# Fixed_Delay_Line.net
KiCad netlist of a schematic drawn in Altium Designer
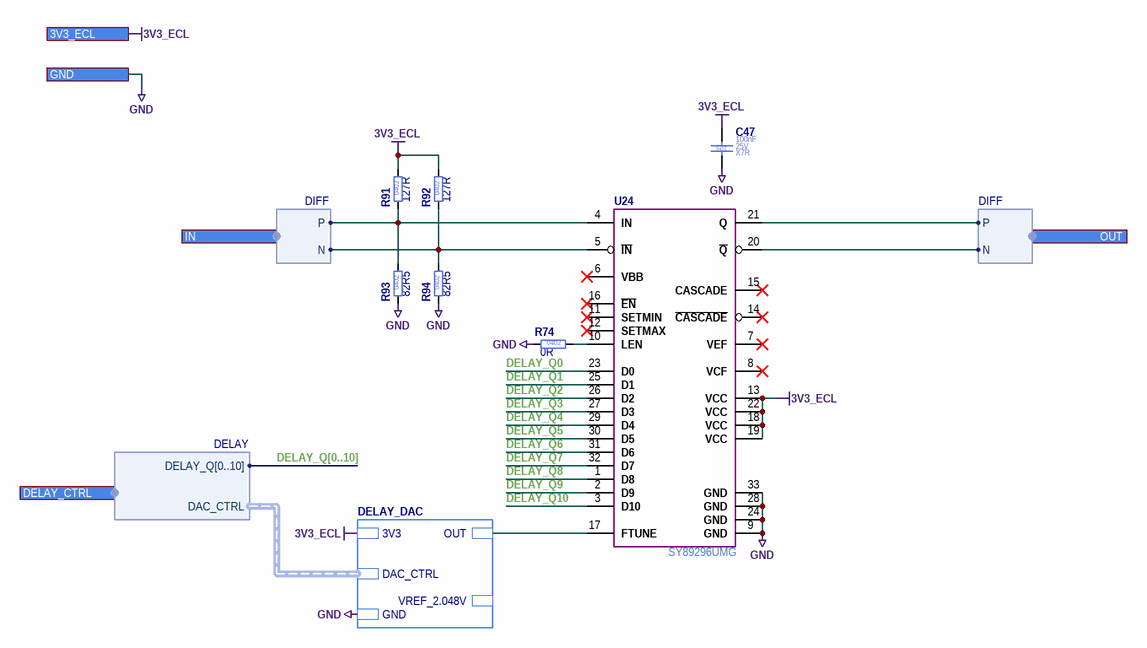
[diagram p0: Fixed_Delay_Line.SchDoc]

(export (version "E")
  (design (tool "Eeschema 10.0.6"))
  (components
    (comp (ref "C47")
      (value "C_100NF_25V_X7R_0402_10")
      (footprint "C_0402_1005")
      (description "Ceramic Capacitor")
      (fields
        (field (name "CASE/PACKAGE") "0402")
        (field (name "VOLTAGE RATING (DC)") "25V")
        (field (name "DIELECTRIC") "X7R")
        (field (name "CAPACITANCE") "100nF")
        (field (name "TOLERANCE") "10%")
        (field (name "MANUFACTURER PART NUMBER") "EMK105B7104KV-F")
      )
      (libsource (lib "7Sigma") (part "C"))
    )
    (comp (ref "R74")
      (value "R_0R_0402_1")
      (footprint "R_0402_1005")
      (description "Thick Film Resistor")
      (fields
        (field (name "RESISTANCE") "0R")
        (field (name "CASE/PACKAGE") "0402")
        (field (name "TOLERANCE") "1%")
        (field (name "MANUFACTURER") "Yageo")
      )
      (libsource (lib "7Sigma") (part "R"))
    )
    (comp (ref "R91")
      (value "R_127R_0402_1")
      (footprint "R_0402_1005")
      (description "Thick Film Resistor")
      (fields
        (field (name "RESISTANCE") "127R")
        (field (name "CASE/PACKAGE") "0402")
        (field (name "TOLERANCE") "1%")
        (field (name "MANUFACTURER") "Yageo")
      )
      (libsource (lib "7Sigma") (part "R"))
    )
    (comp (ref "R92")
      (value "R_127R_0402_1")
      (footprint "R_0402_1005")
      (description "Thick Film Resistor")
      (fields
        (field (name "RESISTANCE") "127R")
        (field (name "CASE/PACKAGE") "0402")
        (field (name "TOLERANCE") "1%")
        (field (name "MANUFACTURER") "Yageo")
      )
      (libsource (lib "7Sigma") (part "R"))
    )
    (comp (ref "R93")
      (value "R_82R5_0402_1")
      (footprint "R_0402_1005")
      (description "Thick Film Resistor")
      (fields
        (field (name "RESISTANCE") "82R5")
        (field (name "CASE/PACKAGE") "0402")
        (field (name "TOLERANCE") "1%")
        (field (name "MANUFACTURER") "Yageo")
      )
      (libsource (lib "7Sigma") (part "R"))
    )
    (comp (ref "R94")
      (value "R_82R5_0402_1")
      (footprint "R_0402_1005")
      (description "Thick Film Resistor")
      (fields
        (field (name "RESISTANCE") "82R5")
        (field (name "CASE/PACKAGE") "0402")
        (field (name "TOLERANCE") "1%")
        (field (name "MANUFACTURER") "Yageo")
      )
      (libsource (lib "7Sigma") (part "R"))
    )
    (comp (ref "U24")
      (value "SY89296UMG")
      (footprint "QFN50P500X500X100_HS-33N")
      (description "Delay Lines/Timing Elements 2.5V/3.3V PECL Delay Line")
      (fields
        (field (name "MANUFACTURER") "Microchip")
        (field (name "MANUFACTURER PART NUMBER") "SY89296UMG")
      )
      (libsource (lib "7Sigma") (part "SY89296U"))
    )
  )
  (nets
    (net (code "5") (name "/DELAY_Q0") (class "Default")
      (node (ref "U24") (pin "23") (pinfunction "D0_23") (pintype "passive"))
    )
    (net (code "6") (name "/DELAY_Q1") (class "Default")
      (node (ref "U24") (pin "25") (pinfunction "D1_25") (pintype "passive"))
    )
    (net (code "7") (name "/DELAY_Q2") (class "Default")
      (node (ref "U24") (pin "26") (pinfunction "D2_26") (pintype "passive"))
    )
    (net (code "8") (name "/DELAY_Q3") (class "Default")
      (node (ref "U24") (pin "27") (pinfunction "D3_27") (pintype "passive"))
    )
    (net (code "9") (name "/DELAY_Q4") (class "Default")
      (node (ref "U24") (pin "29") (pinfunction "D4_29") (pintype "passive"))
    )
    (net (code "10") (name "/DELAY_Q5") (class "Default")
      (node (ref "U24") (pin "30") (pinfunction "D5_30") (pintype "passive"))
    )
    (net (code "11") (name "/DELAY_Q6") (class "Default")
      (node (ref "U24") (pin "31") (pinfunction "D6_31") (pintype "passive"))
    )
    (net (code "12") (name "/DELAY_Q7") (class "Default")
      (node (ref "U24") (pin "32") (pinfunction "D7_32") (pintype "passive"))
    )
    (net (code "13") (name "/DELAY_Q8") (class "Default")
      (node (ref "U24") (pin "1") (pinfunction "D8_1") (pintype "passive"))
    )
    (net (code "14") (name "/DELAY_Q9") (class "Default")
      (node (ref "U24") (pin "2") (pinfunction "D9_2") (pintype "passive"))
    )
    (net (code "15") (name "/DELAY_Q10") (class "Default")
      (node (ref "U24") (pin "3") (pinfunction "D10_3") (pintype "passive"))
    )
    (net (code "17") (name "/OUT") (class "Default")
      (node (ref "U24") (pin "17") (pinfunction "FTUNE_17") (pintype "passive"))
    )
    (net (code "21") (name "3V3_ECL") (class "Default")
      (node (ref "C47") (pin "1") (pinfunction "1_1") (pintype "passive"))
      (node (ref "R91") (pin "2") (pinfunction "2_2") (pintype "passive"))
      (node (ref "R92") (pin "2") (pinfunction "2_2") (pintype "passive"))
      (node (ref "U24") (pin "13") (pinfunction "VCC_13") (pintype "passive"))
      (node (ref "U24") (pin "18") (pinfunction "VCC_18") (pintype "passive"))
      (node (ref "U24") (pin "19") (pinfunction "VCC_19") (pintype "passive"))
      (node (ref "U24") (pin "22") (pinfunction "VCC_22") (pintype "passive"))
    )
    (net (code "22") (name "GND") (class "Default")
      (node (ref "C47") (pin "2") (pinfunction "2_2") (pintype "passive"))
      (node (ref "R74") (pin "1") (pinfunction "1_1") (pintype "passive"))
      (node (ref "R93") (pin "1") (pinfunction "1_1") (pintype "passive"))
      (node (ref "R94") (pin "1") (pinfunction "1_1") (pintype "passive"))
      (node (ref "U24") (pin "24") (pinfunction "GND_24") (pintype "passive"))
      (node (ref "U24") (pin "28") (pinfunction "GND_28") (pintype "passive"))
      (node (ref "U24") (pin "33") (pinfunction "GND_33") (pintype "passive"))
      (node (ref "U24") (pin "9") (pinfunction "GND_9") (pintype "passive"))
    )
    (net (code "23") (name "Net-(R91-Pad1)") (class "Default")
      (node (ref "R91") (pin "1") (pinfunction "1_1") (pintype "passive"))
      (node (ref "R93") (pin "2") (pinfunction "2_2") (pintype "passive"))
      (node (ref "U24") (pin "4") (pinfunction "IN_4") (pintype "passive"))
    )
    (net (code "24") (name "Net-(R92-Pad1)") (class "Default")
      (node (ref "R92") (pin "1") (pinfunction "1_1") (pintype "passive"))
      (node (ref "R94") (pin "2") (pinfunction "2_2") (pintype "passive"))
      (node (ref "U24") (pin "5") (pinfunction "IN_5") (pintype "passive"))
    )
    (net (code "25") (name "Net-(U24-LEN)") (class "Default")
      (node (ref "R74") (pin "2") (pinfunction "2_2") (pintype "passive"))
      (node (ref "U24") (pin "10") (pinfunction "LEN_10") (pintype "passive"))
    )
    (net (code "26") (name "unconnected-(U24-CASCADE-Pad14)") (class "Default")
      (node (ref "U24") (pin "14") (pinfunction "CASCADE_14") (pintype "passive+no_connect"))
    )
    (net (code "27") (name "unconnected-(U24-CASCADE-Pad15)") (class "Default")
      (node (ref "U24") (pin "15") (pinfunction "CASCADE_15") (pintype "passive+no_connect"))
    )
    (net (code "28") (name "unconnected-(U24-EN-Pad16)") (class "Default")
      (node (ref "U24") (pin "16") (pinfunction "EN_16") (pintype "passive+no_connect"))
    )
    (net (code "29") (name "unconnected-(U24-Q-Pad20)") (class "Default")
      (node (ref "U24") (pin "20") (pinfunction "Q_20") (pintype "passive"))
    )
    (net (code "30") (name "unconnected-(U24-Q-Pad21)") (class "Default")
      (node (ref "U24") (pin "21") (pinfunction "Q_21") (pintype "passive"))
    )
    (net (code "31") (name "unconnected-(U24-SETMAX-Pad12)") (class "Default")
      (node (ref "U24") (pin "12") (pinfunction "SETMAX_12") (pintype "passive+no_connect"))
    )
    (net (code "32") (name "unconnected-(U24-SETMIN-Pad11)") (class "Default")
      (node (ref "U24") (pin "11") (pinfunction "SETMIN_11") (pintype "passive+no_connect"))
    )
    (net (code "33") (name "unconnected-(U24-VBB-Pad6)") (class "Default")
      (node (ref "U24") (pin "6") (pinfunction "VBB_6") (pintype "passive+no_connect"))
    )
    (net (code "34") (name "unconnected-(U24-VCF-Pad8)") (class "Default")
      (node (ref "U24") (pin "8") (pinfunction "VCF_8") (pintype "passive+no_connect"))
    )
    (net (code "35") (name "unconnected-(U24-VEF-Pad7)") (class "Default")
      (node (ref "U24") (pin "7") (pinfunction "VEF_7") (pintype "passive+no_connect"))
    )
  )
)
